# protection.net
KiCad netlist of a schematic drawn in EAGLE
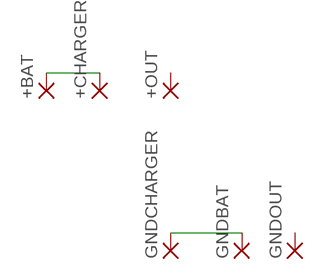
[diagram p0: schematic, sheet 1]

(export (version "E")
  (design (tool "Eeschema 10.0.6"))
  (components
    (comp (ref "+BAT")
      (value "1,6/0,8")
      (footprint "eagle-import:1,6_0,8")
      (libsource (lib "eagle-import") (part "1,6/0,8"))
    )
    (comp (ref "+CHARGER")
      (value "1,6/0,8")
      (footprint "eagle-import:1,6_0,8")
      (libsource (lib "eagle-import") (part "1,6/0,8"))
    )
    (comp (ref "+OUT")
      (value "1,6/0,8")
      (footprint "eagle-import:1,6_0,8")
      (libsource (lib "eagle-import") (part "1,6/0,8"))
    )
    (comp (ref "GNDBAT")
      (value "1,6/0,8")
      (footprint "eagle-import:1,6_0,8")
      (libsource (lib "eagle-import") (part "1,6/0,8"))
    )
    (comp (ref "GNDCHARGER")
      (value "1,6/0,8")
      (footprint "eagle-import:1,6_0,8")
      (libsource (lib "eagle-import") (part "1,6/0,8"))
    )
    (comp (ref "GNDOUT")
      (value "1,6/0,8")
      (footprint "eagle-import:1,6_0,8")
      (libsource (lib "eagle-import") (part "1,6/0,8"))
    )
  )
  (nets
    (net (code "1") (name "Net-(+BAT-P)") (class "Default")
      (node (ref "+BAT") (pin "1") (pinfunction "P_1") (pintype "passive"))
      (node (ref "+CHARGER") (pin "1") (pinfunction "P_1") (pintype "passive"))
    )
    (net (code "2") (name "Net-(GNDBAT-P)") (class "Default")
      (node (ref "GNDBAT") (pin "1") (pinfunction "P_1") (pintype "passive"))
      (node (ref "GNDCHARGER") (pin "1") (pinfunction "P_1") (pintype "passive"))
    )
    (net (code "3") (name "unconnected-(+OUT-P-Pad1)") (class "Default")
      (node (ref "+OUT") (pin "1") (pinfunction "P_1") (pintype "passive"))
    )
    (net (code "4") (name "unconnected-(GNDOUT-P-Pad1)") (class "Default")
      (node (ref "GNDOUT") (pin "1") (pinfunction "P_1") (pintype "passive"))
    )
  )
)
